# Power_supply.net
KiCad netlist of a schematic drawn in Altium Designer
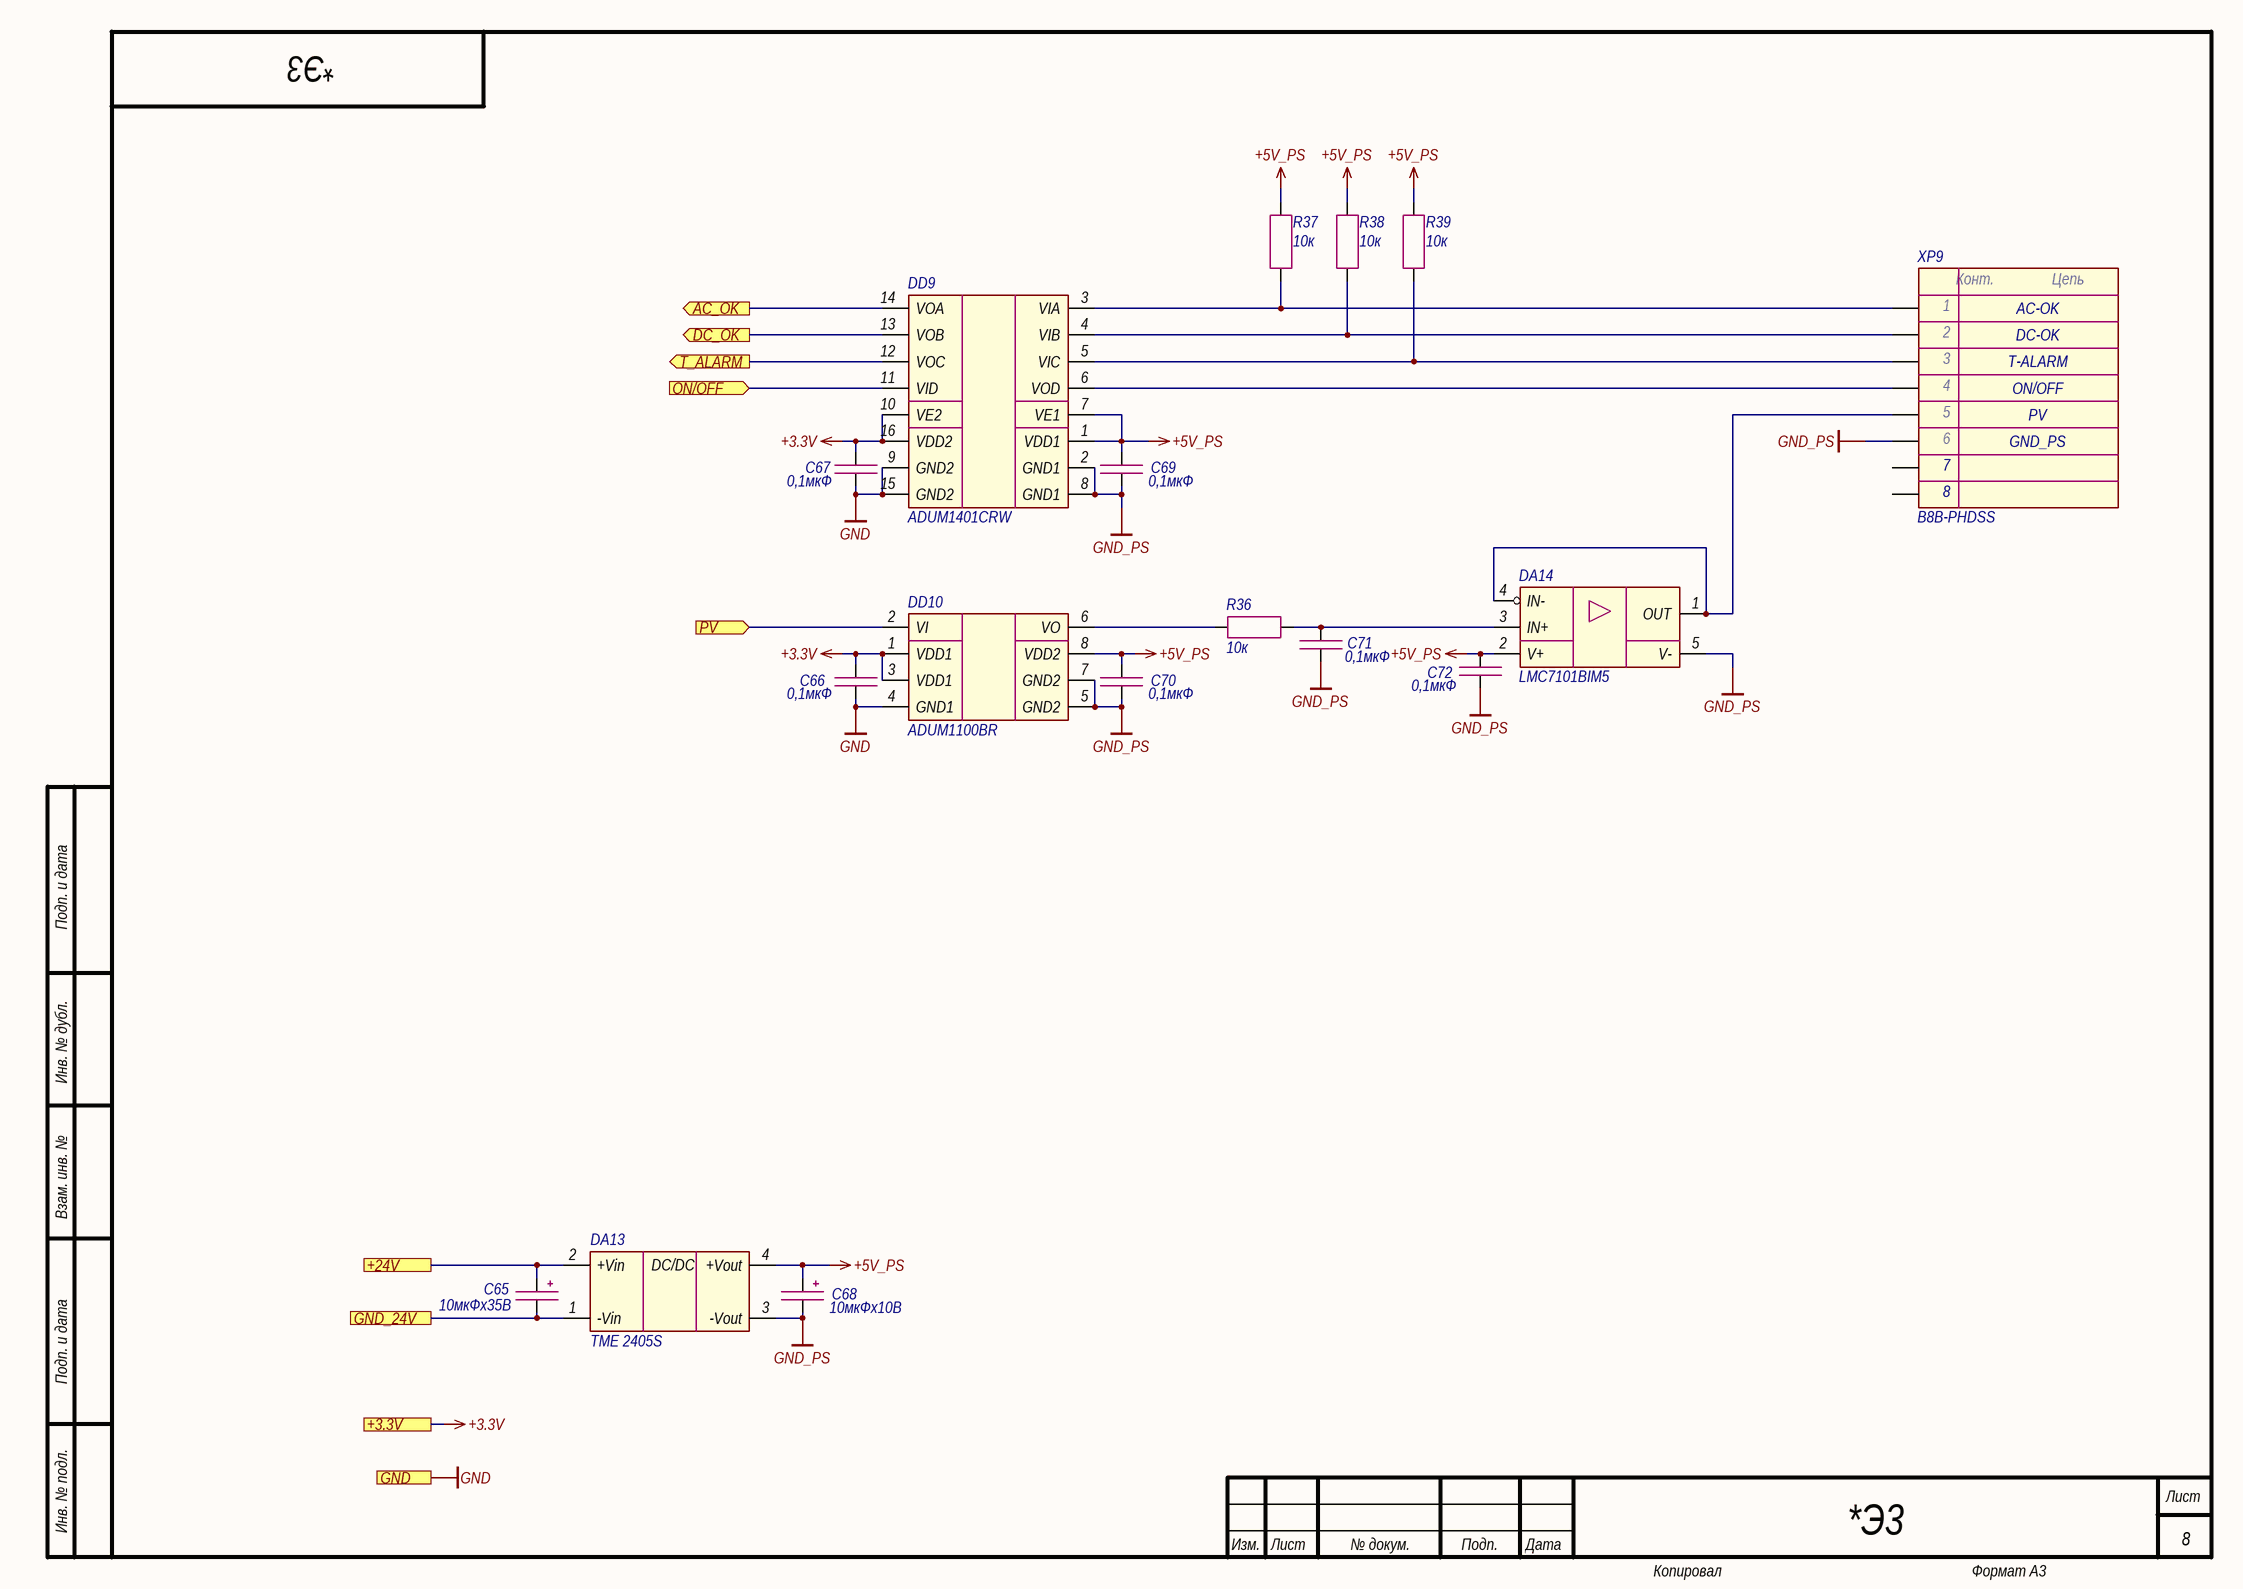
[diagram p0: Power_supply.SchDoc]

(export (version "E")
  (design (tool "Eeschema 10.0.6"))
  (components
    (comp (ref "C65")
      (value "10мкФх35B")
      (footprint "Pcb_library:CAP_C")
      (libsource (lib "Schem_library") (part "Capacitor_Polar"))
    )
    (comp (ref "C66")
      (value "0,1мкФ")
      (footprint "Pcb_library:CAP_0603")
      (fields (field (name "MANUFACTURER") "Murata"))
      (libsource (lib "Schem_library") (part "Capacitor"))
    )
    (comp (ref "C67")
      (value "0,1мкФ")
      (footprint "Pcb_library:CAP_0603")
      (fields (field (name "MANUFACTURER") "Murata"))
      (libsource (lib "Schem_library") (part "Capacitor"))
    )
    (comp (ref "C68")
      (value "10мкФх10B")
      (footprint "Pcb_library:CAP_A")
      (libsource (lib "Schem_library") (part "Capacitor_Polar"))
    )
    (comp (ref "C69")
      (value "0,1мкФ")
      (footprint "Pcb_library:CAP_0603")
      (fields (field (name "MANUFACTURER") "Murata"))
      (libsource (lib "Schem_library") (part "Capacitor"))
    )
    (comp (ref "C70")
      (value "0,1мкФ")
      (footprint "Pcb_library:CAP_0603")
      (fields (field (name "MANUFACTURER") "Murata"))
      (libsource (lib "Schem_library") (part "Capacitor"))
    )
    (comp (ref "C71")
      (value "0,1мкФ")
      (footprint "Pcb_library:CAP_0603")
      (fields (field (name "MANUFACTURER") "Murata"))
      (libsource (lib "Schem_library") (part "Capacitor"))
    )
    (comp (ref "C72")
      (value "0,1мкФ")
      (footprint "Pcb_library:CAP_0603")
      (fields (field (name "MANUFACTURER") "Murata"))
      (libsource (lib "Schem_library") (part "Capacitor"))
    )
    (comp (ref "DA13")
      (value "TME 2405S")
      (footprint "Pcb_library:TME (SIP-4)")
      (fields (field (name "MANUFACTURER") "Traco Power"))
      (libsource (lib "Schem_library") (part "TME"))
    )
    (comp (ref "DA14")
      (value "LMC7101BIM5")
      (footprint "Pcb_library:SOT-23-5")
      (fields (field (name "MANUFACTURER") "Texas Instruments"))
      (libsource (lib "Schem_library") (part "LMC7101"))
    )
    (comp (ref "DD9")
      (value "ADUM1401CRW")
      (footprint "Pcb_library:SOIC-16W")
      (fields (field (name "MANUFACTURER") "Analog Devices"))
      (libsource (lib "Schem_library") (part "ADUM1401"))
    )
    (comp (ref "DD10")
      (value "ADUM1100BR")
      (footprint "Pcb_library:SOIC-8")
      (fields (field (name "MANUFACTURER") "Analog Devices"))
      (libsource (lib "Schem_library") (part "ADUM1100"))
    )
    (comp (ref "R36")
      (value "10к")
      (footprint "Pcb_library:RES_0603")
      (fields (field (name "MANUFACTURER") "Yageo"))
      (libsource (lib "Schem_library") (part "Resistor"))
    )
    (comp (ref "R37")
      (value "10к")
      (footprint "Pcb_library:RES_0603")
      (fields (field (name "MANUFACTURER") "Yageo"))
      (libsource (lib "Schem_library") (part "Resistor"))
    )
    (comp (ref "R38")
      (value "10к")
      (footprint "Pcb_library:RES_0603")
      (fields (field (name "MANUFACTURER") "Yageo"))
      (libsource (lib "Schem_library") (part "Resistor"))
    )
    (comp (ref "R39")
      (value "10к")
      (footprint "Pcb_library:RES_0603")
      (fields (field (name "MANUFACTURER") "Yageo"))
      (libsource (lib "Schem_library") (part "Resistor"))
    )
    (comp (ref "XP9")
      (value "B8B-PHDSS")
      (footprint "Pcb_library:B8B-PHDSS")
      (fields (field (name "MANUFACTURER") "JST"))
      (libsource (lib "Schem_library") (part "Connector-8"))
    )
  )
  (nets
    (net (code "1") (name "+3.3V") (class "Default")
      (node (ref "C66") (pin "1") (pinfunction "1_1") (pintype "passive"))
      (node (ref "C67") (pin "1") (pinfunction "1_1") (pintype "passive"))
      (node (ref "DD10") (pin "1") (pinfunction "VDD1_1") (pintype "passive"))
      (node (ref "DD10") (pin "3") (pinfunction "VDD1_3") (pintype "passive"))
      (node (ref "DD9") (pin "10") (pinfunction "VE2_10") (pintype "passive"))
      (node (ref "DD9") (pin "16") (pinfunction "VDD2_16") (pintype "passive"))
    )
    (net (code "2") (name "+5V_PS") (class "Default")
      (node (ref "C68") (pin "1") (pinfunction "1_1") (pintype "passive"))
      (node (ref "C69") (pin "1") (pinfunction "1_1") (pintype "passive"))
      (node (ref "C70") (pin "1") (pinfunction "1_1") (pintype "passive"))
      (node (ref "C72") (pin "1") (pinfunction "1_1") (pintype "passive"))
      (node (ref "DA13") (pin "4") (pinfunction "+Vout_4") (pintype "passive"))
      (node (ref "DA14") (pin "2") (pinfunction "V+_2") (pintype "passive"))
      (node (ref "DD10") (pin "8") (pinfunction "VDD2_8") (pintype "passive"))
      (node (ref "DD9") (pin "1") (pinfunction "VDD1_1") (pintype "passive"))
      (node (ref "DD9") (pin "7") (pinfunction "VE1_7") (pintype "passive"))
      (node (ref "R37") (pin "1") (pinfunction "1_1") (pintype "passive"))
      (node (ref "R38") (pin "1") (pinfunction "1_1") (pintype "passive"))
      (node (ref "R39") (pin "1") (pinfunction "1_1") (pintype "passive"))
    )
    (net (code "3") (name "/+24V") (class "Default")
      (node (ref "C65") (pin "1") (pinfunction "1_1") (pintype "passive"))
      (node (ref "DA13") (pin "2") (pinfunction "+Vin_2") (pintype "passive"))
    )
    (net (code "4") (name "/AC_OK") (class "Default")
      (node (ref "DD9") (pin "14") (pinfunction "VOA_14") (pintype "passive"))
    )
    (net (code "5") (name "/DC_OK") (class "Default")
      (node (ref "DD9") (pin "13") (pinfunction "VOB_13") (pintype "passive"))
    )
    (net (code "6") (name "/GND_24V") (class "Default")
      (node (ref "C65") (pin "2") (pinfunction "2_2") (pintype "passive"))
      (node (ref "DA13") (pin "1") (pinfunction "-Vin_1") (pintype "passive"))
    )
    (net (code "7") (name "/ON{slash}OFF") (class "Default")
      (node (ref "DD9") (pin "11") (pinfunction "VID_11") (pintype "passive"))
    )
    (net (code "8") (name "/PV") (class "Default")
      (node (ref "DD10") (pin "2") (pinfunction "VI_2") (pintype "passive"))
    )
    (net (code "9") (name "/T_ALARM") (class "Default")
      (node (ref "DD9") (pin "12") (pinfunction "VOC_12") (pintype "passive"))
    )
    (net (code "10") (name "GND") (class "Default")
      (node (ref "C66") (pin "2") (pinfunction "2_2") (pintype "passive"))
      (node (ref "C67") (pin "2") (pinfunction "2_2") (pintype "passive"))
      (node (ref "DD10") (pin "4") (pinfunction "GND1_4") (pintype "passive"))
      (node (ref "DD9") (pin "15") (pinfunction "GND2_15") (pintype "passive"))
      (node (ref "DD9") (pin "9") (pinfunction "GND2_9") (pintype "passive"))
    )
    (net (code "11") (name "GND_PS") (class "Default")
      (node (ref "C68") (pin "2") (pinfunction "2_2") (pintype "passive"))
      (node (ref "C69") (pin "2") (pinfunction "2_2") (pintype "passive"))
      (node (ref "C70") (pin "2") (pinfunction "2_2") (pintype "passive"))
      (node (ref "C71") (pin "2") (pinfunction "2_2") (pintype "passive"))
      (node (ref "C72") (pin "2") (pinfunction "2_2") (pintype "passive"))
      (node (ref "DA13") (pin "3") (pinfunction "-Vout_3") (pintype "passive"))
      (node (ref "DA14") (pin "5") (pinfunction "V-_5") (pintype "passive"))
      (node (ref "DD10") (pin "5") (pinfunction "GND2_5") (pintype "passive"))
      (node (ref "DD10") (pin "7") (pinfunction "GND2_7") (pintype "passive"))
      (node (ref "DD9") (pin "2") (pinfunction "GND1_2") (pintype "passive"))
      (node (ref "DD9") (pin "8") (pinfunction "GND1_8") (pintype "passive"))
      (node (ref "XP9") (pin "6") (pintype "passive"))
    )
    (net (code "12") (name "Net-(DA14-IN+)") (class "Default")
      (node (ref "C71") (pin "1") (pinfunction "1_1") (pintype "passive"))
      (node (ref "DA14") (pin "3") (pinfunction "IN+_3") (pintype "passive"))
      (node (ref "R36") (pin "2") (pinfunction "2_2") (pintype "passive"))
    )
    (net (code "13") (name "Net-(DA14-IN-)") (class "Default")
      (node (ref "DA14") (pin "1") (pinfunction "OUT_1") (pintype "passive"))
      (node (ref "DA14") (pin "4") (pinfunction "IN-_4") (pintype "passive"))
      (node (ref "XP9") (pin "5") (pintype "passive"))
    )
    (net (code "14") (name "Net-(DD9-VIA)") (class "Default")
      (node (ref "DD9") (pin "3") (pinfunction "VIA_3") (pintype "passive"))
      (node (ref "R37") (pin "2") (pinfunction "2_2") (pintype "passive"))
      (node (ref "XP9") (pin "1") (pintype "passive"))
    )
    (net (code "15") (name "Net-(DD9-VIB)") (class "Default")
      (node (ref "DD9") (pin "4") (pinfunction "VIB_4") (pintype "passive"))
      (node (ref "R38") (pin "2") (pinfunction "2_2") (pintype "passive"))
      (node (ref "XP9") (pin "2") (pintype "passive"))
    )
    (net (code "16") (name "Net-(DD9-VIC)") (class "Default")
      (node (ref "DD9") (pin "5") (pinfunction "VIC_5") (pintype "passive"))
      (node (ref "R39") (pin "2") (pinfunction "2_2") (pintype "passive"))
      (node (ref "XP9") (pin "3") (pintype "passive"))
    )
    (net (code "17") (name "Net-(DD9-VOD)") (class "Default")
      (node (ref "DD9") (pin "6") (pinfunction "VOD_6") (pintype "passive"))
      (node (ref "XP9") (pin "4") (pintype "passive"))
    )
    (net (code "18") (name "Net-(DD10-VO)") (class "Default")
      (node (ref "DD10") (pin "6") (pinfunction "VO_6") (pintype "passive"))
      (node (ref "R36") (pin "1") (pinfunction "1_1") (pintype "passive"))
    )
    (net (code "19") (name "unconnected-(XP9-Pad7)") (class "Default")
      (node (ref "XP9") (pin "7") (pintype "passive"))
    )
    (net (code "20") (name "unconnected-(XP9-Pad8)") (class "Default")
      (node (ref "XP9") (pin "8") (pintype "passive"))
    )
  )
)
